# Sheet_1__2__22_11_2023__2023-11-22.net
KiCad netlist of a schematic drawn in Altium Designer
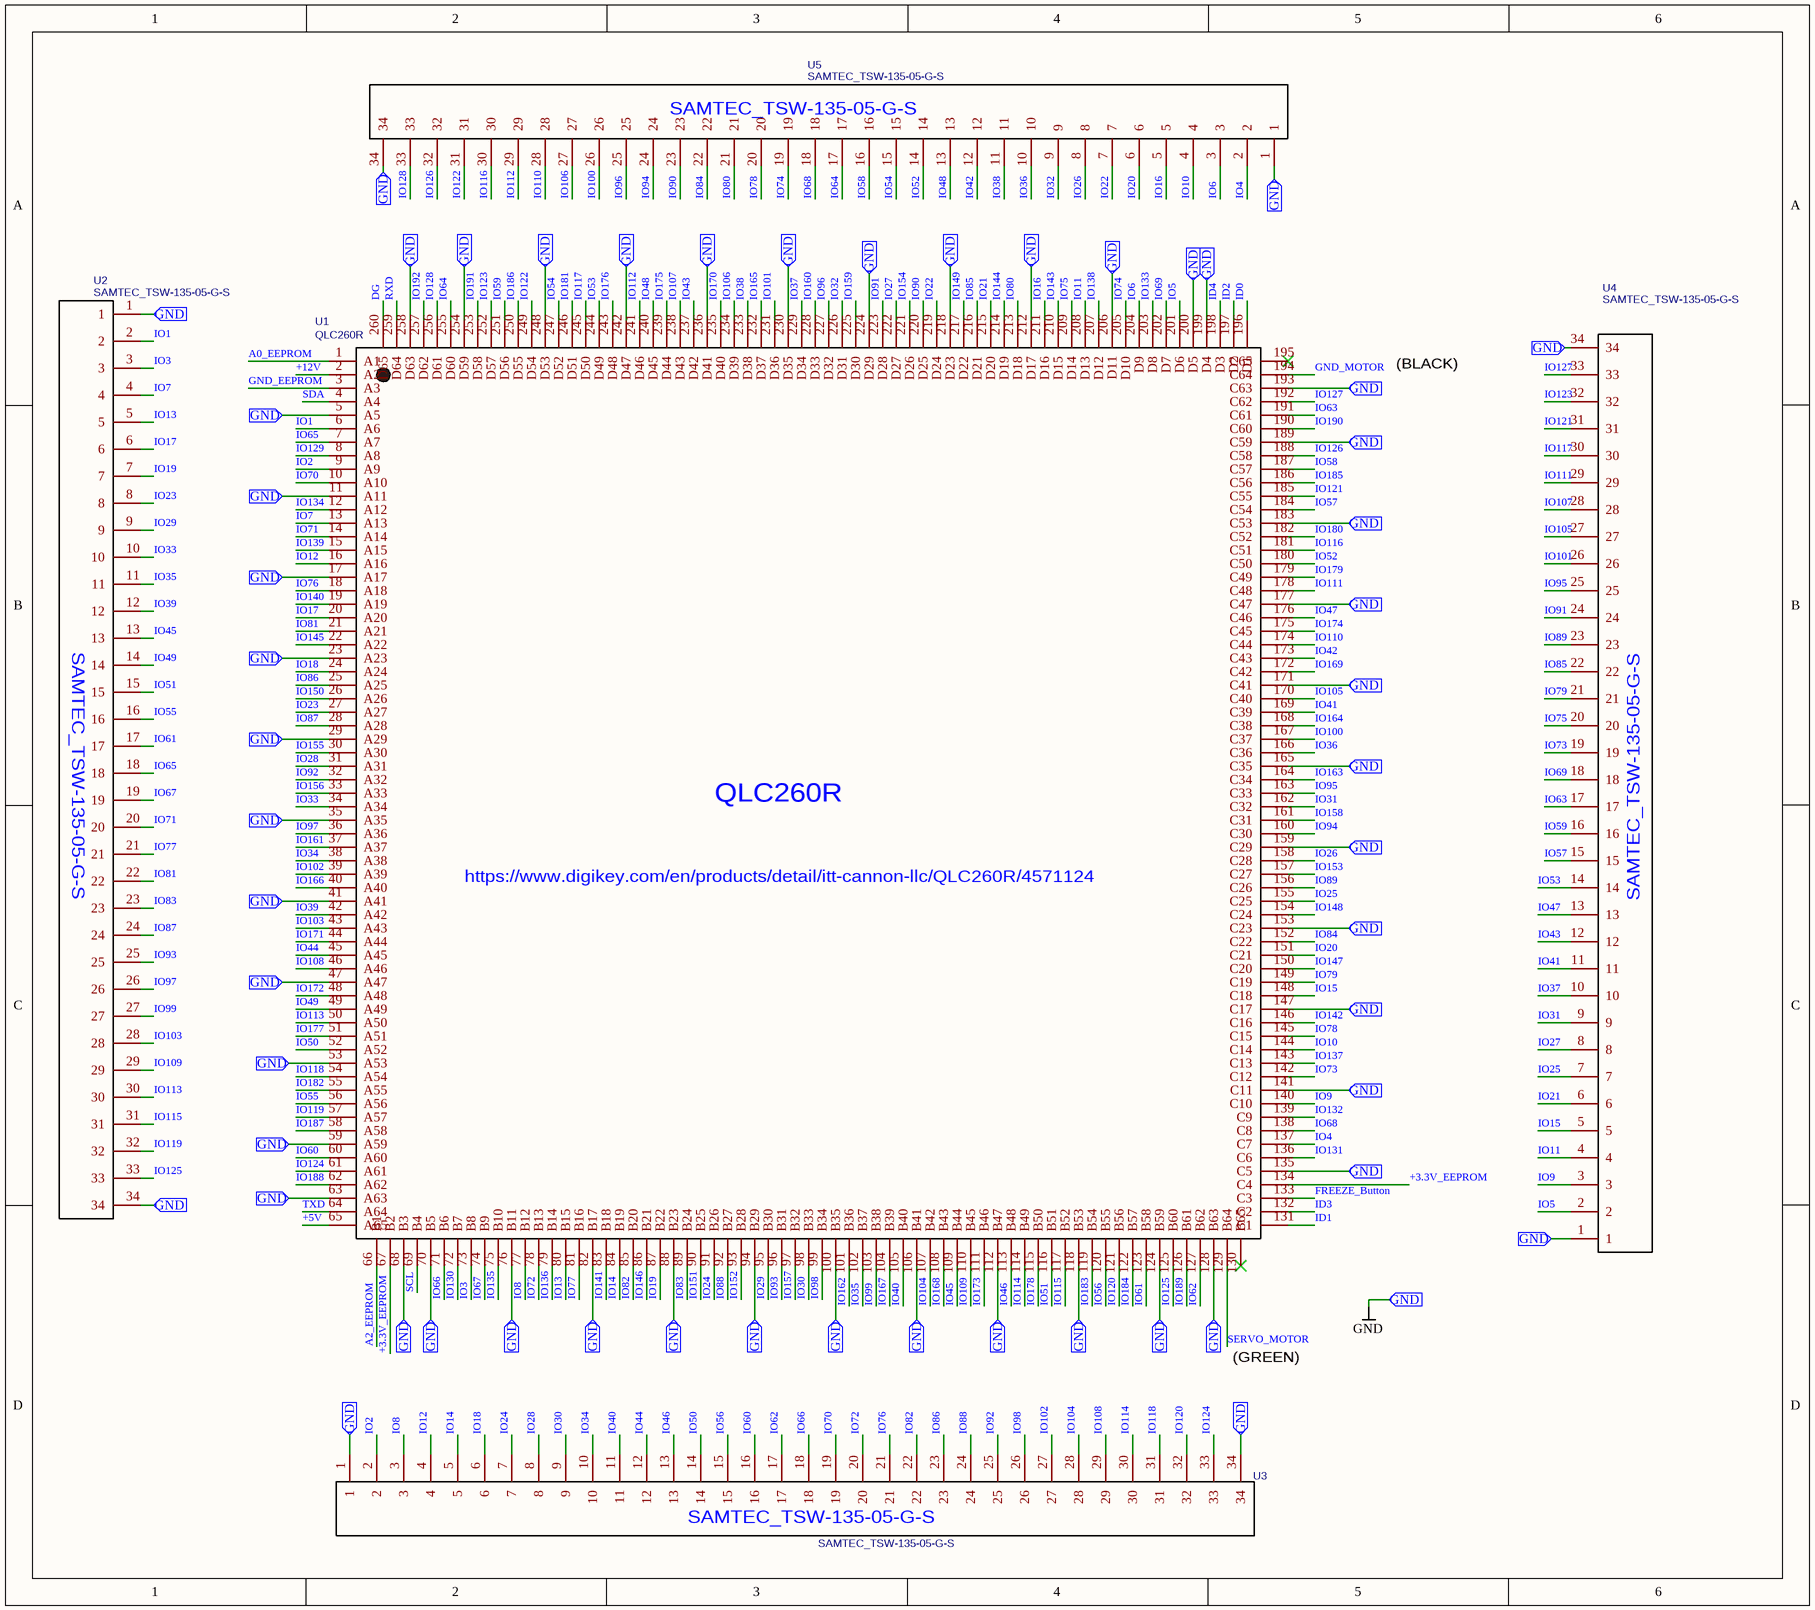
[diagram p0: Sheet_1_(2)_22.11.2023 _2023-11-22.schdoc]

(export (version "E")
  (design (tool "Eeschema 10.0.6"))
  (components
    (comp (ref "U1")
      (value "QLC260R")
      (fields (field (name "MANUFACTURER") "ITT Cannon, LLC") (field (name "CONTRIBUTOR") "venkatakrishnanr"))
      (libsource (lib "altium-import") (part "root_0_QLC260R_"))
    )
    (comp (ref "U2")
      (value "SAMTEC_TSW-135-05-G-S")
      (fields
        (field (name "MANUFACTURER") "Samtec Inc.")
        (field (name "MANUFACTURER PART") "TSW-135-05-G-S")
        (field (name "CONTRIBUTOR") "venkatakrishnanr")
      )
      (libsource (lib "altium-import") (part "root_3_SAMTEC_TSW-135-05-G-S_"))
    )
    (comp (ref "U3")
      (value "SAMTEC_TSW-135-05-G-S")
      (fields
        (field (name "MANUFACTURER") "Samtec Inc.")
        (field (name "MANUFACTURER PART") "TSW-135-05-G-S")
        (field (name "CONTRIBUTOR") "venkatakrishnanr")
      )
      (libsource (lib "altium-import") (part "root_0_SAMTEC_TSW-135-05-G-S_"))
    )
    (comp (ref "U4")
      (value "SAMTEC_TSW-135-05-G-S")
      (fields
        (field (name "MANUFACTURER") "Samtec Inc.")
        (field (name "MANUFACTURER PART") "TSW-135-05-G-S")
        (field (name "CONTRIBUTOR") "venkatakrishnanr")
      )
      (libsource (lib "altium-import") (part "root_1_SAMTEC_TSW-135-05-G-S_"))
    )
    (comp (ref "U5")
      (value "SAMTEC_TSW-135-05-G-S")
      (fields
        (field (name "MANUFACTURER") "Samtec Inc.")
        (field (name "MANUFACTURER PART") "TSW-135-05-G-S")
        (field (name "CONTRIBUTOR") "venkatakrishnanr")
      )
      (libsource (lib "altium-import") (part "root_2_SAMTEC_TSW-135-05-G-S_"))
    )
  )
  (nets
    (net (code "1") (name "/+3.3V_EEPROM") (class "Default")
      (node (ref "U1") (pin "134") (pinfunction "C4_134") (pintype "passive"))
      (node (ref "U1") (pin "67") (pinfunction "B2_67") (pintype "passive"))
    )
    (net (code "2") (name "/+5V") (class "Default")
      (node (ref "U1") (pin "65") (pinfunction "A65_65") (pintype "passive"))
    )
    (net (code "3") (name "/+12V") (class "Default")
      (node (ref "U1") (pin "2") (pinfunction "A2_2") (pintype "passive"))
    )
    (net (code "4") (name "/A0_EEPROM") (class "Default")
      (node (ref "U1") (pin "1") (pinfunction "A1_1") (pintype "passive"))
    )
    (net (code "5") (name "/A2_EEPROM") (class "Default")
      (node (ref "U1") (pin "66") (pinfunction "B1_66") (pintype "passive"))
    )
    (net (code "6") (name "/DG") (class "Default")
      (node (ref "U1") (pin "260") (pinfunction "D65_260") (pintype "passive"))
    )
    (net (code "7") (name "/FREEZE_Button") (class "Default")
      (node (ref "U1") (pin "133") (pinfunction "C3_133") (pintype "passive"))
    )
    (net (code "8") (name "/GND_EEPROM") (class "Default")
      (node (ref "U1") (pin "3") (pinfunction "A3_3") (pintype "passive"))
    )
    (net (code "9") (name "/GND_MOTOR") (class "Default")
      (node (ref "U1") (pin "194") (pinfunction "C64_194") (pintype "passive"))
    )
    (net (code "10") (name "/ID0") (class "Default")
      (node (ref "U1") (pin "196") (pinfunction "D1_196") (pintype "passive"))
    )
    (net (code "11") (name "/ID1") (class "Default")
      (node (ref "U1") (pin "131") (pinfunction "C1_131") (pintype "passive"))
    )
    (net (code "12") (name "/ID2") (class "Default")
      (node (ref "U1") (pin "197") (pinfunction "D2_197") (pintype "passive"))
    )
    (net (code "13") (name "/ID3") (class "Default")
      (node (ref "U1") (pin "132") (pinfunction "C2_132") (pintype "passive"))
    )
    (net (code "14") (name "/ID4") (class "Default")
      (node (ref "U1") (pin "198") (pinfunction "D3_198") (pintype "passive"))
    )
    (net (code "15") (name "/IO1") (class "Default")
      (node (ref "U1") (pin "6") (pinfunction "A6_6") (pintype "passive"))
      (node (ref "U2") (pin "2") (pinfunction "2_2") (pintype "passive"))
    )
    (net (code "16") (name "/IO2") (class "Default")
      (node (ref "U1") (pin "9") (pinfunction "A9_9") (pintype "passive"))
      (node (ref "U3") (pin "2") (pinfunction "2_2") (pintype "passive"))
    )
    (net (code "17") (name "/IO3") (class "Default")
      (node (ref "U1") (pin "73") (pinfunction "B8_73") (pintype "passive"))
      (node (ref "U2") (pin "3") (pinfunction "3_3") (pintype "passive"))
    )
    (net (code "18") (name "/IO4") (class "Default")
      (node (ref "U1") (pin "137") (pinfunction "C7_137") (pintype "passive"))
      (node (ref "U5") (pin "2") (pinfunction "2_2") (pintype "passive"))
    )
    (net (code "19") (name "/IO5") (class "Default")
      (node (ref "U1") (pin "201") (pinfunction "D6_201") (pintype "passive"))
      (node (ref "U4") (pin "2") (pinfunction "2_2") (pintype "passive"))
    )
    (net (code "20") (name "/IO6") (class "Default")
      (node (ref "U1") (pin "204") (pinfunction "D9_204") (pintype "passive"))
      (node (ref "U5") (pin "3") (pinfunction "3_3") (pintype "passive"))
    )
    (net (code "21") (name "/IO7") (class "Default")
      (node (ref "U1") (pin "13") (pinfunction "A13_13") (pintype "passive"))
      (node (ref "U2") (pin "4") (pinfunction "4_4") (pintype "passive"))
    )
    (net (code "22") (name "/IO8") (class "Default")
      (node (ref "U1") (pin "77") (pinfunction "B12_77") (pintype "passive"))
      (node (ref "U3") (pin "3") (pinfunction "3_3") (pintype "passive"))
    )
    (net (code "23") (name "/IO9") (class "Default")
      (node (ref "U1") (pin "140") (pinfunction "C10_140") (pintype "passive"))
      (node (ref "U4") (pin "3") (pinfunction "3_3") (pintype "passive"))
    )
    (net (code "24") (name "/IO10") (class "Default")
      (node (ref "U1") (pin "144") (pinfunction "C14_144") (pintype "passive"))
      (node (ref "U5") (pin "4") (pinfunction "4_4") (pintype "passive"))
    )
    (net (code "25") (name "/IO11") (class "Default")
      (node (ref "U1") (pin "208") (pinfunction "D13_208") (pintype "passive"))
      (node (ref "U4") (pin "4") (pinfunction "4_4") (pintype "passive"))
    )
    (net (code "26") (name "/IO12") (class "Default")
      (node (ref "U1") (pin "16") (pinfunction "A16_16") (pintype "passive"))
      (node (ref "U3") (pin "4") (pinfunction "4_4") (pintype "passive"))
    )
    (net (code "27") (name "/IO13") (class "Default")
      (node (ref "U1") (pin "80") (pinfunction "B15_80") (pintype "passive"))
      (node (ref "U2") (pin "5") (pinfunction "5_5") (pintype "passive"))
    )
    (net (code "28") (name "/IO14") (class "Default")
      (node (ref "U1") (pin "84") (pinfunction "B19_84") (pintype "passive"))
      (node (ref "U3") (pin "5") (pinfunction "5_5") (pintype "passive"))
    )
    (net (code "29") (name "/IO15") (class "Default")
      (node (ref "U1") (pin "148") (pinfunction "C18_148") (pintype "passive"))
      (node (ref "U4") (pin "5") (pinfunction "5_5") (pintype "passive"))
    )
    (net (code "30") (name "/IO16") (class "Default")
      (node (ref "U1") (pin "211") (pinfunction "D16_211") (pintype "passive"))
      (node (ref "U5") (pin "5") (pinfunction "5_5") (pintype "passive"))
    )
    (net (code "31") (name "/IO17") (class "Default")
      (node (ref "U1") (pin "20") (pinfunction "A20_20") (pintype "passive"))
      (node (ref "U2") (pin "6") (pinfunction "6_6") (pintype "passive"))
    )
    (net (code "32") (name "/IO18") (class "Default")
      (node (ref "U1") (pin "24") (pinfunction "A24_24") (pintype "passive"))
      (node (ref "U3") (pin "6") (pinfunction "6_6") (pintype "passive"))
    )
    (net (code "33") (name "/IO19") (class "Default")
      (node (ref "U1") (pin "87") (pinfunction "B22_87") (pintype "passive"))
      (node (ref "U2") (pin "7") (pinfunction "7_7") (pintype "passive"))
    )
    (net (code "34") (name "/IO20") (class "Default")
      (node (ref "U1") (pin "151") (pinfunction "C21_151") (pintype "passive"))
      (node (ref "U5") (pin "6") (pinfunction "6_6") (pintype "passive"))
    )
    (net (code "35") (name "/IO21") (class "Default")
      (node (ref "U1") (pin "215") (pinfunction "D20_215") (pintype "passive"))
      (node (ref "U4") (pin "6") (pinfunction "6_6") (pintype "passive"))
    )
    (net (code "36") (name "/IO22") (class "Default")
      (node (ref "U1") (pin "219") (pinfunction "D24_219") (pintype "passive"))
      (node (ref "U5") (pin "7") (pinfunction "7_7") (pintype "passive"))
    )
    (net (code "37") (name "/IO23") (class "Default")
      (node (ref "U1") (pin "27") (pinfunction "A27_27") (pintype "passive"))
      (node (ref "U2") (pin "8") (pinfunction "8_8") (pintype "passive"))
    )
    (net (code "38") (name "/IO24") (class "Default")
      (node (ref "U1") (pin "91") (pinfunction "B26_91") (pintype "passive"))
      (node (ref "U3") (pin "7") (pinfunction "7_7") (pintype "passive"))
    )
    (net (code "39") (name "/IO25") (class "Default")
      (node (ref "U1") (pin "155") (pinfunction "C25_155") (pintype "passive"))
      (node (ref "U4") (pin "7") (pinfunction "7_7") (pintype "passive"))
    )
    (net (code "40") (name "/IO26") (class "Default")
      (node (ref "U1") (pin "158") (pinfunction "C28_158") (pintype "passive"))
      (node (ref "U5") (pin "8") (pinfunction "8_8") (pintype "passive"))
    )
    (net (code "41") (name "/IO27") (class "Default")
      (node (ref "U1") (pin "222") (pinfunction "D27_222") (pintype "passive"))
      (node (ref "U4") (pin "8") (pinfunction "8_8") (pintype "passive"))
    )
    (net (code "42") (name "/IO28") (class "Default")
      (node (ref "U1") (pin "31") (pinfunction "A31_31") (pintype "passive"))
      (node (ref "U3") (pin "8") (pinfunction "8_8") (pintype "passive"))
    )
    (net (code "43") (name "/IO29") (class "Default")
      (node (ref "U1") (pin "95") (pinfunction "B30_95") (pintype "passive"))
      (node (ref "U2") (pin "9") (pinfunction "9_9") (pintype "passive"))
    )
    (net (code "44") (name "/IO30") (class "Default")
      (node (ref "U1") (pin "98") (pinfunction "B33_98") (pintype "passive"))
      (node (ref "U3") (pin "9") (pinfunction "9_9") (pintype "passive"))
    )
    (net (code "45") (name "/IO31") (class "Default")
      (node (ref "U1") (pin "162") (pinfunction "C32_162") (pintype "passive"))
      (node (ref "U4") (pin "9") (pinfunction "9_9") (pintype "passive"))
    )
    (net (code "46") (name "/IO32") (class "Default")
      (node (ref "U1") (pin "226") (pinfunction "D31_226") (pintype "passive"))
      (node (ref "U5") (pin "9") (pinfunction "9_9") (pintype "passive"))
    )
    (net (code "47") (name "/IO33") (class "Default")
      (node (ref "U1") (pin "34") (pinfunction "A34_34") (pintype "passive"))
      (node (ref "U2") (pin "10") (pinfunction "10_10") (pintype "passive"))
    )
    (net (code "48") (name "/IO34") (class "Default")
      (node (ref "U1") (pin "38") (pinfunction "A38_38") (pintype "passive"))
      (node (ref "U3") (pin "10") (pinfunction "10_10") (pintype "passive"))
    )
    (net (code "49") (name "/IO35") (class "Default")
      (node (ref "U1") (pin "102") (pinfunction "B37_102") (pintype "passive"))
      (node (ref "U2") (pin "11") (pinfunction "11_11") (pintype "passive"))
    )
    (net (code "50") (name "/IO36") (class "Default")
      (node (ref "U1") (pin "166") (pinfunction "C36_166") (pintype "passive"))
      (node (ref "U5") (pin "10") (pinfunction "10_10") (pintype "passive"))
    )
    (net (code "51") (name "/IO37") (class "Default")
      (node (ref "U1") (pin "229") (pinfunction "D34_229") (pintype "passive"))
      (node (ref "U4") (pin "10") (pinfunction "10_10") (pintype "passive"))
    )
    (net (code "52") (name "/IO38") (class "Default")
      (node (ref "U1") (pin "233") (pinfunction "D38_233") (pintype "passive"))
      (node (ref "U5") (pin "11") (pinfunction "11_11") (pintype "passive"))
    )
    (net (code "53") (name "/IO39") (class "Default")
      (node (ref "U1") (pin "42") (pinfunction "A42_42") (pintype "passive"))
      (node (ref "U2") (pin "12") (pinfunction "12_12") (pintype "passive"))
    )
    (net (code "54") (name "/IO40") (class "Default")
      (node (ref "U1") (pin "105") (pinfunction "B40_105") (pintype "passive"))
      (node (ref "U3") (pin "11") (pinfunction "11_11") (pintype "passive"))
    )
    (net (code "55") (name "/IO41") (class "Default")
      (node (ref "U1") (pin "169") (pinfunction "C39_169") (pintype "passive"))
      (node (ref "U4") (pin "11") (pinfunction "11_11") (pintype "passive"))
    )
    (net (code "56") (name "/IO42") (class "Default")
      (node (ref "U1") (pin "173") (pinfunction "C43_173") (pintype "passive"))
      (node (ref "U5") (pin "12") (pinfunction "12_12") (pintype "passive"))
    )
    (net (code "57") (name "/IO43") (class "Default")
      (node (ref "U1") (pin "237") (pinfunction "D42_237") (pintype "passive"))
      (node (ref "U4") (pin "12") (pinfunction "12_12") (pintype "passive"))
    )
    (net (code "58") (name "/IO44") (class "Default")
      (node (ref "U1") (pin "45") (pinfunction "A45_45") (pintype "passive"))
      (node (ref "U3") (pin "12") (pinfunction "12_12") (pintype "passive"))
    )
    (net (code "59") (name "/IO45") (class "Default")
      (node (ref "U1") (pin "109") (pinfunction "B44_109") (pintype "passive"))
      (node (ref "U2") (pin "13") (pinfunction "13_13") (pintype "passive"))
    )
    (net (code "60") (name "/IO46") (class "Default")
      (node (ref "U1") (pin "113") (pinfunction "B48_113") (pintype "passive"))
      (node (ref "U3") (pin "13") (pinfunction "13_13") (pintype "passive"))
    )
    (net (code "61") (name "/IO47") (class "Default")
      (node (ref "U1") (pin "176") (pinfunction "C46_176") (pintype "passive"))
      (node (ref "U4") (pin "13") (pinfunction "13_13") (pintype "passive"))
    )
    (net (code "62") (name "/IO48") (class "Default")
      (node (ref "U1") (pin "240") (pinfunction "D45_240") (pintype "passive"))
      (node (ref "U5") (pin "13") (pinfunction "13_13") (pintype "passive"))
    )
    (net (code "63") (name "/IO49") (class "Default")
      (node (ref "U1") (pin "49") (pinfunction "A49_49") (pintype "passive"))
      (node (ref "U2") (pin "14") (pinfunction "14_14") (pintype "passive"))
    )
    (net (code "64") (name "/IO50") (class "Default")
      (node (ref "U1") (pin "52") (pinfunction "A52_52") (pintype "passive"))
      (node (ref "U3") (pin "14") (pinfunction "14_14") (pintype "passive"))
    )
    (net (code "65") (name "/IO51") (class "Default")
      (node (ref "U1") (pin "116") (pinfunction "B51_116") (pintype "passive"))
      (node (ref "U2") (pin "15") (pinfunction "15_15") (pintype "passive"))
    )
    (net (code "66") (name "/IO52") (class "Default")
      (node (ref "U1") (pin "180") (pinfunction "C50_180") (pintype "passive"))
      (node (ref "U5") (pin "14") (pinfunction "14_14") (pintype "passive"))
    )
    (net (code "67") (name "/IO53") (class "Default")
      (node (ref "U1") (pin "244") (pinfunction "D49_244") (pintype "passive"))
      (node (ref "U4") (pin "14") (pinfunction "14_14") (pintype "passive"))
    )
    (net (code "68") (name "/IO54") (class "Default")
      (node (ref "U1") (pin "247") (pinfunction "D52_247") (pintype "passive"))
      (node (ref "U5") (pin "15") (pinfunction "15_15") (pintype "passive"))
    )
    (net (code "69") (name "/IO55") (class "Default")
      (node (ref "U1") (pin "56") (pinfunction "A56_56") (pintype "passive"))
      (node (ref "U2") (pin "16") (pinfunction "16_16") (pintype "passive"))
    )
    (net (code "70") (name "/IO56") (class "Default")
      (node (ref "U1") (pin "120") (pinfunction "B55_120") (pintype "passive"))
      (node (ref "U3") (pin "15") (pinfunction "15_15") (pintype "passive"))
    )
    (net (code "71") (name "/IO57") (class "Default")
      (node (ref "U1") (pin "184") (pinfunction "C54_184") (pintype "passive"))
      (node (ref "U4") (pin "15") (pinfunction "15_15") (pintype "passive"))
    )
    (net (code "72") (name "/IO58") (class "Default")
      (node (ref "U1") (pin "187") (pinfunction "C57_187") (pintype "passive"))
      (node (ref "U5") (pin "16") (pinfunction "16_16") (pintype "passive"))
    )
    (net (code "73") (name "/IO59") (class "Default")
      (node (ref "U1") (pin "251") (pinfunction "D56_251") (pintype "passive"))
      (node (ref "U4") (pin "16") (pinfunction "16_16") (pintype "passive"))
    )
    (net (code "74") (name "/IO60") (class "Default")
      (node (ref "U1") (pin "60") (pinfunction "A60_60") (pintype "passive"))
      (node (ref "U3") (pin "16") (pinfunction "16_16") (pintype "passive"))
    )
    (net (code "75") (name "/IO61") (class "Default")
      (node (ref "U1") (pin "123") (pinfunction "B58_123") (pintype "passive"))
      (node (ref "U2") (pin "17") (pinfunction "17_17") (pintype "passive"))
    )
    (net (code "76") (name "/IO62") (class "Default")
      (node (ref "U1") (pin "127") (pinfunction "B62_127") (pintype "passive"))
      (node (ref "U3") (pin "17") (pinfunction "17_17") (pintype "passive"))
    )
    (net (code "77") (name "/IO63") (class "Default")
      (node (ref "U1") (pin "191") (pinfunction "C61_191") (pintype "passive"))
      (node (ref "U4") (pin "17") (pinfunction "17_17") (pintype "passive"))
    )
    (net (code "78") (name "/IO64") (class "Default")
      (node (ref "U1") (pin "255") (pinfunction "D60_255") (pintype "passive"))
      (node (ref "U5") (pin "17") (pinfunction "17_17") (pintype "passive"))
    )
    (net (code "79") (name "/IO65") (class "Default")
      (node (ref "U1") (pin "7") (pinfunction "A7_7") (pintype "passive"))
      (node (ref "U2") (pin "18") (pinfunction "18_18") (pintype "passive"))
    )
    (net (code "80") (name "/IO66") (class "Default")
      (node (ref "U1") (pin "71") (pinfunction "B6_71") (pintype "passive"))
      (node (ref "U3") (pin "18") (pinfunction "18_18") (pintype "passive"))
    )
    (net (code "81") (name "/IO67") (class "Default")
      (node (ref "U1") (pin "74") (pinfunction "B9_74") (pintype "passive"))
      (node (ref "U2") (pin "19") (pinfunction "19_19") (pintype "passive"))
    )
    (net (code "82") (name "/IO68") (class "Default")
      (node (ref "U1") (pin "138") (pinfunction "C8_138") (pintype "passive"))
      (node (ref "U5") (pin "18") (pinfunction "18_18") (pintype "passive"))
    )
    (net (code "83") (name "/IO69") (class "Default")
      (node (ref "U1") (pin "202") (pinfunction "D7_202") (pintype "passive"))
      (node (ref "U4") (pin "18") (pinfunction "18_18") (pintype "passive"))
    )
    (net (code "84") (name "/IO70") (class "Default")
      (node (ref "U1") (pin "10") (pinfunction "A10_10") (pintype "passive"))
      (node (ref "U3") (pin "19") (pinfunction "19_19") (pintype "passive"))
    )
    (net (code "85") (name "/IO71") (class "Default")
      (node (ref "U1") (pin "14") (pinfunction "A14_14") (pintype "passive"))
      (node (ref "U2") (pin "20") (pinfunction "20_20") (pintype "passive"))
    )
    (net (code "86") (name "/IO72") (class "Default")
      (node (ref "U1") (pin "78") (pinfunction "B13_78") (pintype "passive"))
      (node (ref "U3") (pin "20") (pinfunction "20_20") (pintype "passive"))
    )
    (net (code "87") (name "/IO73") (class "Default")
      (node (ref "U1") (pin "142") (pinfunction "C12_142") (pintype "passive"))
      (node (ref "U4") (pin "19") (pinfunction "19_19") (pintype "passive"))
    )
    (net (code "88") (name "/IO74") (class "Default")
      (node (ref "U1") (pin "205") (pinfunction "D10_205") (pintype "passive"))
      (node (ref "U5") (pin "19") (pinfunction "19_19") (pintype "passive"))
    )
    (net (code "89") (name "/IO75") (class "Default")
      (node (ref "U1") (pin "209") (pinfunction "D14_209") (pintype "passive"))
      (node (ref "U4") (pin "20") (pinfunction "20_20") (pintype "passive"))
    )
    (net (code "90") (name "/IO76") (class "Default")
      (node (ref "U1") (pin "18") (pinfunction "A18_18") (pintype "passive"))
      (node (ref "U3") (pin "21") (pinfunction "21_21") (pintype "passive"))
    )
    (net (code "91") (name "/IO77") (class "Default")
      (node (ref "U1") (pin "81") (pinfunction "B16_81") (pintype "passive"))
      (node (ref "U2") (pin "21") (pinfunction "21_21") (pintype "passive"))
    )
    (net (code "92") (name "/IO78") (class "Default")
      (node (ref "U1") (pin "145") (pinfunction "C15_145") (pintype "passive"))
      (node (ref "U5") (pin "20") (pinfunction "20_20") (pintype "passive"))
    )
    (net (code "93") (name "/IO79") (class "Default")
      (node (ref "U1") (pin "149") (pinfunction "C19_149") (pintype "passive"))
      (node (ref "U4") (pin "21") (pinfunction "21_21") (pintype "passive"))
    )
    (net (code "94") (name "/IO80") (class "Default")
      (node (ref "U1") (pin "213") (pinfunction "D18_213") (pintype "passive"))
      (node (ref "U5") (pin "21") (pinfunction "21_21") (pintype "passive"))
    )
    (net (code "95") (name "/IO81") (class "Default")
      (node (ref "U1") (pin "21") (pinfunction "A21_21") (pintype "passive"))
      (node (ref "U2") (pin "22") (pinfunction "22_22") (pintype "passive"))
    )
    (net (code "96") (name "/IO82") (class "Default")
      (node (ref "U1") (pin "85") (pinfunction "B20_85") (pintype "passive"))
      (node (ref "U3") (pin "22") (pinfunction "22_22") (pintype "passive"))
    )
    (net (code "97") (name "/IO83") (class "Default")
      (node (ref "U1") (pin "89") (pinfunction "B24_89") (pintype "passive"))
      (node (ref "U2") (pin "23") (pinfunction "23_23") (pintype "passive"))
    )
    (net (code "98") (name "/IO84") (class "Default")
      (node (ref "U1") (pin "152") (pinfunction "C22_152") (pintype "passive"))
      (node (ref "U5") (pin "22") (pinfunction "22_22") (pintype "passive"))
    )
    (net (code "99") (name "/IO85") (class "Default")
      (node (ref "U1") (pin "216") (pinfunction "D21_216") (pintype "passive"))
      (node (ref "U4") (pin "22") (pinfunction "22_22") (pintype "passive"))
    )
    (net (code "100") (name "/IO86") (class "Default")
      (node (ref "U1") (pin "25") (pinfunction "A25_25") (pintype "passive"))
      (node (ref "U3") (pin "23") (pinfunction "23_23") (pintype "passive"))
    )
    (net (code "101") (name "/IO87") (class "Default")
      (node (ref "U1") (pin "28") (pinfunction "A28_28") (pintype "passive"))
      (node (ref "U2") (pin "24") (pinfunction "24_24") (pintype "passive"))
    )
    (net (code "102") (name "/IO88") (class "Default")
      (node (ref "U1") (pin "92") (pinfunction "B27_92") (pintype "passive"))
      (node (ref "U3") (pin "24") (pinfunction "24_24") (pintype "passive"))
    )
    (net (code "103") (name "/IO89") (class "Default")
      (node (ref "U1") (pin "156") (pinfunction "C26_156") (pintype "passive"))
      (node (ref "U4") (pin "23") (pinfunction "23_23") (pintype "passive"))
    )
    (net (code "104") (name "/IO90") (class "Default")
      (node (ref "U1") (pin "220") (pinfunction "D25_220") (pintype "passive"))
      (node (ref "U5") (pin "23") (pinfunction "23_23") (pintype "passive"))
    )
    (net (code "105") (name "/IO91") (class "Default")
      (node (ref "U1") (pin "223") (pinfunction "D28_223") (pintype "passive"))
      (node (ref "U4") (pin "24") (pinfunction "24_24") (pintype "passive"))
    )
    (net (code "106") (name "/IO92") (class "Default")
      (node (ref "U1") (pin "32") (pinfunction "A32_32") (pintype "passive"))
      (node (ref "U3") (pin "25") (pinfunction "25_25") (pintype "passive"))
    )
    (net (code "107") (name "/IO93") (class "Default")
      (node (ref "U1") (pin "96") (pinfunction "B31_96") (pintype "passive"))
      (node (ref "U2") (pin "25") (pinfunction "25_25") (pintype "passive"))
    )
    (net (code "108") (name "/IO94") (class "Default")
      (node (ref "U1") (pin "160") (pinfunction "C30_160") (pintype "passive"))
      (node (ref "U5") (pin "24") (pinfunction "24_24") (pintype "passive"))
    )
    (net (code "109") (name "/IO95") (class "Default")
      (node (ref "U1") (pin "163") (pinfunction "C33_163") (pintype "passive"))
      (node (ref "U4") (pin "25") (pinfunction "25_25") (pintype "passive"))
    )
    (net (code "110") (name "/IO96") (class "Default")
      (node (ref "U1") (pin "227") (pinfunction "D32_227") (pintype "passive"))
      (node (ref "U5") (pin "25") (pinfunction "25_25") (pintype "passive"))
    )
    (net (code "111") (name "/IO97") (class "Default")
      (node (ref "U1") (pin "36") (pinfunction "A36_36") (pintype "passive"))
      (node (ref "U2") (pin "26") (pinfunction "26_26") (pintype "passive"))
    )
    (net (code "112") (name "/IO98") (class "Default")
      (node (ref "U1") (pin "99") (pinfunction "B34_99") (pintype "passive"))
      (node (ref "U3") (pin "26") (pinfunction "26_26") (pintype "passive"))
    )
    (net (code "113") (name "/IO99") (class "Default")
      (node (ref "U1") (pin "103") (pinfunction "B38_103") (pintype "passive"))
      (node (ref "U2") (pin "27") (pinfunction "27_27") (pintype "passive"))
    )
    (net (code "114") (name "/IO100") (class "Default")
      (node (ref "U1") (pin "167") (pinfunction "C37_167") (pintype "passive"))
      (node (ref "U5") (pin "26") (pinfunction "26_26") (pintype "passive"))
    )
    (net (code "115") (name "/IO101") (class "Default")
      (node (ref "U1") (pin "231") (pinfunction "D36_231") (pintype "passive"))
      (node (ref "U4") (pin "26") (pinfunction "26_26") (pintype "passive"))
    )
    (net (code "116") (name "/IO102") (class "Default")
      (node (ref "U1") (pin "39") (pinfunction "A39_39") (pintype "passive"))
      (node (ref "U3") (pin "27") (pinfunction "27_27") (pintype "passive"))
    )
    (net (code "117") (name "/IO103") (class "Default")
      (node (ref "U1") (pin "43") (pinfunction "A43_43") (pintype "passive"))
      (node (ref "U2") (pin "28") (pinfunction "28_28") (pintype "passive"))
    )
    (net (code "118") (name "/IO104") (class "Default")
      (node (ref "U1") (pin "107") (pinfunction "B42_107") (pintype "passive"))
      (node (ref "U3") (pin "28") (pinfunction "28_28") (pintype "passive"))
    )
    (net (code "119") (name "/IO105") (class "Default")
      (node (ref "U1") (pin "170") (pinfunction "C40_170") (pintype "passive"))
      (node (ref "U4") (pin "27") (pinfunction "27_27") (pintype "passive"))
    )
    (net (code "120") (name "/IO106") (class "Default")
      (node (ref "U1") (pin "234") (pinfunction "D39_234") (pintype "passive"))
      (node (ref "U5") (pin "27") (pinfunction "27_27") (pintype "passive"))
    )
    (net (code "121") (name "/IO107") (class "Default")
      (node (ref "U1") (pin "238") (pinfunction "D43_238") (pintype "passive"))
      (node (ref "U4") (pin "28") (pinfunction "28_28") (pintype "passive"))
    )
    (net (code "122") (name "/IO108") (class "Default")
      (node (ref "U1") (pin "46") (pinfunction "A46_46") (pintype "passive"))
      (node (ref "U3") (pin "29") (pinfunction "29_29") (pintype "passive"))
    )
    (net (code "123") (name "/IO109") (class "Default")
      (node (ref "U1") (pin "110") (pinfunction "B45_110") (pintype "passive"))
      (node (ref "U2") (pin "29") (pinfunction "29_29") (pintype "passive"))
    )
    (net (code "124") (name "/IO110") (class "Default")
      (node (ref "U1") (pin "174") (pinfunction "C44_174") (pintype "passive"))
      (node (ref "U5") (pin "28") (pinfunction "28_28") (pintype "passive"))
    )
    (net (code "125") (name "/IO111") (class "Default")
      (node (ref "U1") (pin "178") (pinfunction "C48_178") (pintype "passive"))
      (node (ref "U4") (pin "29") (pinfunction "29_29") (pintype "passive"))
    )
    (net (code "126") (name "/IO112") (class "Default")
      (node (ref "U1") (pin "241") (pinfunction "D46_241") (pintype "passive"))
      (node (ref "U5") (pin "29") (pinfunction "29_29") (pintype "passive"))
    )
    (net (code "127") (name "/IO113") (class "Default")
      (node (ref "U1") (pin "50") (pinfunction "A50_50") (pintype "passive"))
      (node (ref "U2") (pin "30") (pinfunction "30_30") (pintype "passive"))
    )
    (net (code "128") (name "/IO114") (class "Default")
      (node (ref "U1") (pin "114") (pinfunction "B49_114") (pintype "passive"))
      (node (ref "U3") (pin "30") (pinfunction "30_30") (pintype "passive"))
    )
    (net (code "129") (name "/IO115") (class "Default")
      (node (ref "U1") (pin "117") (pinfunction "B52_117") (pintype "passive"))
      (node (ref "U2") (pin "31") (pinfunction "31_31") (pintype "passive"))
    )
    (net (code "130") (name "/IO116") (class "Default")
      (node (ref "U1") (pin "181") (pinfunction "C51_181") (pintype "passive"))
      (node (ref "U5") (pin "30") (pinfunction "30_30") (pintype "passive"))
    )
    (net (code "131") (name "/IO117") (class "Default")
      (node (ref "U1") (pin "245") (pinfunction "D50_245") (pintype "passive"))
      (node (ref "U4") (pin "30") (pinfunction "30_30") (pintype "passive"))
    )
    (net (code "132") (name "/IO118") (class "Default")
      (node (ref "U1") (pin "54") (pinfunction "A54_54") (pintype "passive"))
      (node (ref "U3") (pin "31") (pinfunction "31_31") (pintype "passive"))
    )
    (net (code "133") (name "/IO119") (class "Default")
      (node (ref "U1") (pin "57") (pinfunction "A57_57") (pintype "passive"))
      (node (ref "U2") (pin "32") (pinfunction "32_32") (pintype "passive"))
    )
    (net (code "134") (name "/IO120") (class "Default")
      (node (ref "U1") (pin "121") (pinfunction "B56_121") (pintype "passive"))
      (node (ref "U3") (pin "32") (pinfunction "32_32") (pintype "passive"))
    )
    (net (code "135") (name "/IO121") (class "Default")
      (node (ref "U1") (pin "185") (pinfunction "C55_185") (pintype "passive"))
      (node (ref "U4") (pin "31") (pinfunction "31_31") (pintype "passive"))
    )
    (net (code "136") (name "/IO122") (class "Default")
      (node (ref "U1") (pin "249") (pinfunction "D54_249") (pintype "passive"))
      (node (ref "U5") (pin "31") (pinfunction "31_31") (pintype "passive"))
    )
    (net (code "137") (name "/IO123") (class "Default")
      (node (ref "U1") (pin "252") (pinfunction "D57_252") (pintype "passive"))
      (node (ref "U4") (pin "32") (pinfunction "32_32") (pintype "passive"))
    )
    (net (code "138") (name "/IO124") (class "Default")
      (node (ref "U1") (pin "61") (pinfunction "A61_61") (pintype "passive"))
      (node (ref "U3") (pin "33") (pinfunction "33_33") (pintype "passive"))
    )
    (net (code "139") (name "/IO125") (class "Default")
      (node (ref "U1") (pin "125") (pinfunction "B60_125") (pintype "passive"))
      (node (ref "U2") (pin "33") (pinfunction "33_33") (pintype "passive"))
    )
    (net (code "140") (name "/IO126") (class "Default")
      (node (ref "U1") (pin "188") (pinfunction "C58_188") (pintype "passive"))
      (node (ref "U5") (pin "32") (pinfunction "32_32") (pintype "passive"))
    )
    (net (code "141") (name "/IO127") (class "Default")
      (node (ref "U1") (pin "192") (pinfunction "C62_192") (pintype "passive"))
      (node (ref "U4") (pin "33") (pinfunction "33_33") (pintype "passive"))
    )
    (net (code "142") (name "/IO128") (class "Default")
      (node (ref "U1") (pin "256") (pinfunction "D61_256") (pintype "passive"))
      (node (ref "U5") (pin "33") (pinfunction "33_33") (pintype "passive"))
    )
    (net (code "143") (name "/IO129") (class "Default")
      (node (ref "U1") (pin "8") (pinfunction "A8_8") (pintype "passive"))
    )
    (net (code "144") (name "/IO130") (class "Default")
      (node (ref "U1") (pin "72") (pinfunction "B7_72") (pintype "passive"))
    )
    (net (code "145") (name "/IO131") (class "Default")
      (node (ref "U1") (pin "136") (pinfunction "C6_136") (pintype "passive"))
    )
    (net (code "146") (name "/IO132") (class "Default")
      (node (ref "U1") (pin "139") (pinfunction "C9_139") (pintype "passive"))
    )
    (net (code "147") (name "/IO133") (class "Default")
      (node (ref "U1") (pin "203") (pinfunction "D8_203") (pintype "passive"))
    )
    (net (code "148") (name "/IO134") (class "Default")
      (node (ref "U1") (pin "12") (pinfunction "A12_12") (pintype "passive"))
    )
    (net (code "149") (name "/IO135") (class "Default")
      (node (ref "U1") (pin "75") (pinfunction "B10_75") (pintype "passive"))
    )
    (net (code "150") (name "/IO136") (class "Default")
      (node (ref "U1") (pin "79") (pinfunction "B14_79") (pintype "passive"))
    )
    (net (code "151") (name "/IO137") (class "Default")
      (node (ref "U1") (pin "143") (pinfunction "C13_143") (pintype "passive"))
    )
    (net (code "152") (name "/IO138") (class "Default")
      (node (ref "U1") (pin "207") (pinfunction "D12_207") (pintype "passive"))
    )
    (net (code "153") (name "/IO139") (class "Default")
      (node (ref "U1") (pin "15") (pinfunction "A15_15") (pintype "passive"))
    )
    (net (code "154") (name "/IO140") (class "Default")
      (node (ref "U1") (pin "19") (pinfunction "A19_19") (pintype "passive"))
    )
    (net (code "155") (name "/IO141") (class "Default")
      (node (ref "U1") (pin "83") (pinfunction "B18_83") (pintype "passive"))
    )
    (net (code "156") (name "/IO142") (class "Default")
      (node (ref "U1") (pin "146") (pinfunction "C16_146") (pintype "passive"))
    )
    (net (code "157") (name "/IO143") (class "Default")
      (node (ref "U1") (pin "210") (pinfunction "D15_210") (pintype "passive"))
    )
    (net (code "158") (name "/IO144") (class "Default")
      (node (ref "U1") (pin "214") (pinfunction "D19_214") (pintype "passive"))
    )
    (net (code "159") (name "/IO145") (class "Default")
      (node (ref "U1") (pin "22") (pinfunction "A22_22") (pintype "passive"))
    )
    (net (code "160") (name "/IO146") (class "Default")
      (node (ref "U1") (pin "86") (pinfunction "B21_86") (pintype "passive"))
    )
    (net (code "161") (name "/IO147") (class "Default")
      (node (ref "U1") (pin "150") (pinfunction "C20_150") (pintype "passive"))
    )
    (net (code "162") (name "/IO148") (class "Default")
      (node (ref "U1") (pin "154") (pinfunction "C24_154") (pintype "passive"))
    )
    (net (code "163") (name "/IO149") (class "Default")
      (node (ref "U1") (pin "217") (pinfunction "D22_217") (pintype "passive"))
    )
    (net (code "164") (name "/IO150") (class "Default")
      (node (ref "U1") (pin "26") (pinfunction "A26_26") (pintype "passive"))
    )
    (net (code "165") (name "/IO151") (class "Default")
      (node (ref "U1") (pin "90") (pinfunction "B25_90") (pintype "passive"))
    )
    (net (code "166") (name "/IO152") (class "Default")
      (node (ref "U1") (pin "93") (pinfunction "B28_93") (pintype "passive"))
    )
    (net (code "167") (name "/IO153") (class "Default")
      (node (ref "U1") (pin "157") (pinfunction "C27_157") (pintype "passive"))
    )
    (net (code "168") (name "/IO154") (class "Default")
      (node (ref "U1") (pin "221") (pinfunction "D26_221") (pintype "passive"))
    )
    (net (code "169") (name "/IO155") (class "Default")
      (node (ref "U1") (pin "30") (pinfunction "A30_30") (pintype "passive"))
    )
    (net (code "170") (name "/IO156") (class "Default")
      (node (ref "U1") (pin "33") (pinfunction "A33_33") (pintype "passive"))
    )
    (net (code "171") (name "/IO157") (class "Default")
      (node (ref "U1") (pin "97") (pinfunction "B32_97") (pintype "passive"))
    )
    (net (code "172") (name "/IO158") (class "Default")
      (node (ref "U1") (pin "161") (pinfunction "C31_161") (pintype "passive"))
    )
    (net (code "173") (name "/IO159") (class "Default")
      (node (ref "U1") (pin "225") (pinfunction "D30_225") (pintype "passive"))
    )
    (net (code "174") (name "/IO160") (class "Default")
      (node (ref "U1") (pin "228") (pinfunction "D33_228") (pintype "passive"))
    )
    (net (code "175") (name "/IO161") (class "Default")
      (node (ref "U1") (pin "37") (pinfunction "A37_37") (pintype "passive"))
    )
    (net (code "176") (name "/IO162") (class "Default")
      (node (ref "U1") (pin "101") (pinfunction "B36_101") (pintype "passive"))
    )
    (net (code "177") (name "/IO163") (class "Default")
      (node (ref "U1") (pin "164") (pinfunction "C34_164") (pintype "passive"))
    )
    (net (code "178") (name "/IO164") (class "Default")
      (node (ref "U1") (pin "168") (pinfunction "C38_168") (pintype "passive"))
    )
    (net (code "179") (name "/IO165") (class "Default")
      (node (ref "U1") (pin "232") (pinfunction "D37_232") (pintype "passive"))
    )
    (net (code "180") (name "/IO166") (class "Default")
      (node (ref "U1") (pin "40") (pinfunction "A40_40") (pintype "passive"))
    )
    (net (code "181") (name "/IO167") (class "Default")
      (node (ref "U1") (pin "104") (pinfunction "B39_104") (pintype "passive"))
    )
    (net (code "182") (name "/IO168") (class "Default")
      (node (ref "U1") (pin "108") (pinfunction "B43_108") (pintype "passive"))
    )
    (net (code "183") (name "/IO169") (class "Default")
      (node (ref "U1") (pin "172") (pinfunction "C42_172") (pintype "passive"))
    )
    (net (code "184") (name "/IO170") (class "Default")
      (node (ref "U1") (pin "235") (pinfunction "D40_235") (pintype "passive"))
    )
    (net (code "185") (name "/IO171") (class "Default")
      (node (ref "U1") (pin "44") (pinfunction "A44_44") (pintype "passive"))
    )
    (net (code "186") (name "/IO172") (class "Default")
      (node (ref "U1") (pin "48") (pinfunction "A48_48") (pintype "passive"))
    )
    (net (code "187") (name "/IO173") (class "Default")
      (node (ref "U1") (pin "111") (pinfunction "B46_111") (pintype "passive"))
    )
    (net (code "188") (name "/IO174") (class "Default")
      (node (ref "U1") (pin "175") (pinfunction "C45_175") (pintype "passive"))
    )
    (net (code "189") (name "/IO175") (class "Default")
      (node (ref "U1") (pin "239") (pinfunction "D44_239") (pintype "passive"))
    )
    (net (code "190") (name "/IO176") (class "Default")
      (node (ref "U1") (pin "243") (pinfunction "D48_243") (pintype "passive"))
    )
    (net (code "191") (name "/IO177") (class "Default")
      (node (ref "U1") (pin "51") (pinfunction "A51_51") (pintype "passive"))
    )
    (net (code "192") (name "/IO178") (class "Default")
      (node (ref "U1") (pin "115") (pinfunction "B50_115") (pintype "passive"))
    )
    (net (code "193") (name "/IO179") (class "Default")
      (node (ref "U1") (pin "179") (pinfunction "C49_179") (pintype "passive"))
    )
    (net (code "194") (name "/IO180") (class "Default")
      (node (ref "U1") (pin "182") (pinfunction "C52_182") (pintype "passive"))
    )
    (net (code "195") (name "/IO181") (class "Default")
      (node (ref "U1") (pin "246") (pinfunction "D51_246") (pintype "passive"))
    )
    (net (code "196") (name "/IO182") (class "Default")
      (node (ref "U1") (pin "55") (pinfunction "A55_55") (pintype "passive"))
    )
    (net (code "197") (name "/IO183") (class "Default")
      (node (ref "U1") (pin "119") (pinfunction "B54_119") (pintype "passive"))
    )
    (net (code "198") (name "/IO184") (class "Default")
      (node (ref "U1") (pin "122") (pinfunction "B57_122") (pintype "passive"))
    )
    (net (code "199") (name "/IO185") (class "Default")
      (node (ref "U1") (pin "186") (pinfunction "C56_186") (pintype "passive"))
    )
    (net (code "200") (name "/IO186") (class "Default")
      (node (ref "U1") (pin "250") (pinfunction "D55_250") (pintype "passive"))
    )
    (net (code "201") (name "/IO187") (class "Default")
      (node (ref "U1") (pin "58") (pinfunction "A58_58") (pintype "passive"))
    )
    (net (code "202") (name "/IO188") (class "Default")
      (node (ref "U1") (pin "62") (pinfunction "A62_62") (pintype "passive"))
    )
    (net (code "203") (name "/IO189") (class "Default")
      (node (ref "U1") (pin "126") (pinfunction "B61_126") (pintype "passive"))
    )
    (net (code "204") (name "/IO190") (class "Default")
      (node (ref "U1") (pin "190") (pinfunction "C60_190") (pintype "passive"))
    )
    (net (code "205") (name "/IO191") (class "Default")
      (node (ref "U1") (pin "253") (pinfunction "D58_253") (pintype "passive"))
    )
    (net (code "206") (name "/IO192") (class "Default")
      (node (ref "U1") (pin "257") (pinfunction "D62_257") (pintype "passive"))
    )
    (net (code "207") (name "/RXD") (class "Default")
      (node (ref "U1") (pin "259") (pinfunction "D64_259") (pintype "passive"))
    )
    (net (code "208") (name "/SCL") (class "Default")
      (node (ref "U1") (pin "69") (pinfunction "B4_69") (pintype "passive"))
    )
    (net (code "209") (name "/SDA") (class "Default")
      (node (ref "U1") (pin "4") (pinfunction "A4_4") (pintype "passive"))
    )
    (net (code "210") (name "/SERVO_MOTOR") (class "Default")
      (node (ref "U1") (pin "129") (pinfunction "B64_129") (pintype "passive"))
    )
    (net (code "211") (name "/TXD") (class "Default")
      (node (ref "U1") (pin "64") (pinfunction "A64_64") (pintype "passive"))
    )
    (net (code "212") (name "GND") (class "Default")
      (node (ref "U1") (pin "100") (pinfunction "B35_100") (pintype "passive"))
      (node (ref "U1") (pin "106") (pinfunction "B41_106") (pintype "passive"))
      (node (ref "U1") (pin "11") (pinfunction "A11_11") (pintype "passive"))
      (node (ref "U1") (pin "112") (pinfunction "B47_112") (pintype "passive"))
      (node (ref "U1") (pin "118") (pinfunction "B53_118") (pintype "passive"))
      (node (ref "U1") (pin "124") (pinfunction "B59_124") (pintype "passive"))
      (node (ref "U1") (pin "128") (pinfunction "B63_128") (pintype "passive"))
      (node (ref "U1") (pin "135") (pinfunction "C5_135") (pintype "passive"))
      (node (ref "U1") (pin "141") (pinfunction "C11_141") (pintype "passive"))
      (node (ref "U1") (pin "147") (pinfunction "C17_147") (pintype "passive"))
      (node (ref "U1") (pin "153") (pinfunction "C23_153") (pintype "passive"))
      (node (ref "U1") (pin "159") (pinfunction "C29_159") (pintype "passive"))
      (node (ref "U1") (pin "165") (pinfunction "C35_165") (pintype "passive"))
      (node (ref "U1") (pin "17") (pinfunction "A17_17") (pintype "passive"))
      (node (ref "U1") (pin "171") (pinfunction "C41_171") (pintype "passive"))
      (node (ref "U1") (pin "177") (pinfunction "C47_177") (pintype "passive"))
      (node (ref "U1") (pin "183") (pinfunction "C53_183") (pintype "passive"))
      (node (ref "U1") (pin "189") (pinfunction "C59_189") (pintype "passive"))
      (node (ref "U1") (pin "193") (pinfunction "C63_193") (pintype "passive"))
      (node (ref "U1") (pin "199") (pinfunction "D4_199") (pintype "passive"))
      (node (ref "U1") (pin "200") (pinfunction "D5_200") (pintype "passive"))
      (node (ref "U1") (pin "206") (pinfunction "D11_206") (pintype "passive"))
      (node (ref "U1") (pin "212") (pinfunction "D17_212") (pintype "passive"))
      (node (ref "U1") (pin "218") (pinfunction "D23_218") (pintype "passive"))
      (node (ref "U1") (pin "224") (pinfunction "D29_224") (pintype "passive"))
      (node (ref "U1") (pin "23") (pinfunction "A23_23") (pintype "passive"))
      (node (ref "U1") (pin "230") (pinfunction "D35_230") (pintype "passive"))
      (node (ref "U1") (pin "236") (pinfunction "D41_236") (pintype "passive"))
      (node (ref "U1") (pin "242") (pinfunction "D47_242") (pintype "passive"))
      (node (ref "U1") (pin "248") (pinfunction "D53_248") (pintype "passive"))
      (node (ref "U1") (pin "254") (pinfunction "D59_254") (pintype "passive"))
      (node (ref "U1") (pin "258") (pinfunction "D63_258") (pintype "passive"))
      (node (ref "U1") (pin "29") (pinfunction "A29_29") (pintype "passive"))
      (node (ref "U1") (pin "35") (pinfunction "A35_35") (pintype "passive"))
      (node (ref "U1") (pin "41") (pinfunction "A41_41") (pintype "passive"))
      (node (ref "U1") (pin "47") (pinfunction "A47_47") (pintype "passive"))
      (node (ref "U1") (pin "5") (pinfunction "A5_5") (pintype "passive"))
      (node (ref "U1") (pin "53") (pinfunction "A53_53") (pintype "passive"))
      (node (ref "U1") (pin "59") (pinfunction "A59_59") (pintype "passive"))
      (node (ref "U1") (pin "63") (pinfunction "A63_63") (pintype "passive"))
      (node (ref "U1") (pin "68") (pinfunction "B3_68") (pintype "passive"))
      (node (ref "U1") (pin "70") (pinfunction "B5_70") (pintype "passive"))
      (node (ref "U1") (pin "76") (pinfunction "B11_76") (pintype "passive"))
      (node (ref "U1") (pin "82") (pinfunction "B17_82") (pintype "passive"))
      (node (ref "U1") (pin "88") (pinfunction "B23_88") (pintype "passive"))
      (node (ref "U1") (pin "94") (pinfunction "B29_94") (pintype "passive"))
      (node (ref "U2") (pin "1") (pinfunction "1_1") (pintype "passive"))
      (node (ref "U2") (pin "34") (pinfunction "34_34") (pintype "passive"))
      (node (ref "U3") (pin "1") (pinfunction "1_1") (pintype "passive"))
      (node (ref "U3") (pin "34") (pinfunction "34_34") (pintype "passive"))
      (node (ref "U4") (pin "1") (pinfunction "1_1") (pintype "passive"))
      (node (ref "U4") (pin "34") (pinfunction "34_34") (pintype "passive"))
      (node (ref "U5") (pin "1") (pinfunction "1_1") (pintype "passive"))
      (node (ref "U5") (pin "34") (pinfunction "34_34") (pintype "passive"))
    )
    (net (code "213") (name "unconnected-(U1-B65-Pad130)") (class "Default")
      (node (ref "U1") (pin "130") (pinfunction "B65_130") (pintype "passive+no_connect"))
    )
    (net (code "214") (name "unconnected-(U1-C65-Pad195)") (class "Default")
      (node (ref "U1") (pin "195") (pinfunction "C65_195") (pintype "passive+no_connect"))
    )
  )
)
